# mtp_zesilovac.net
KiCad netlist of a schematic drawn in EAGLE
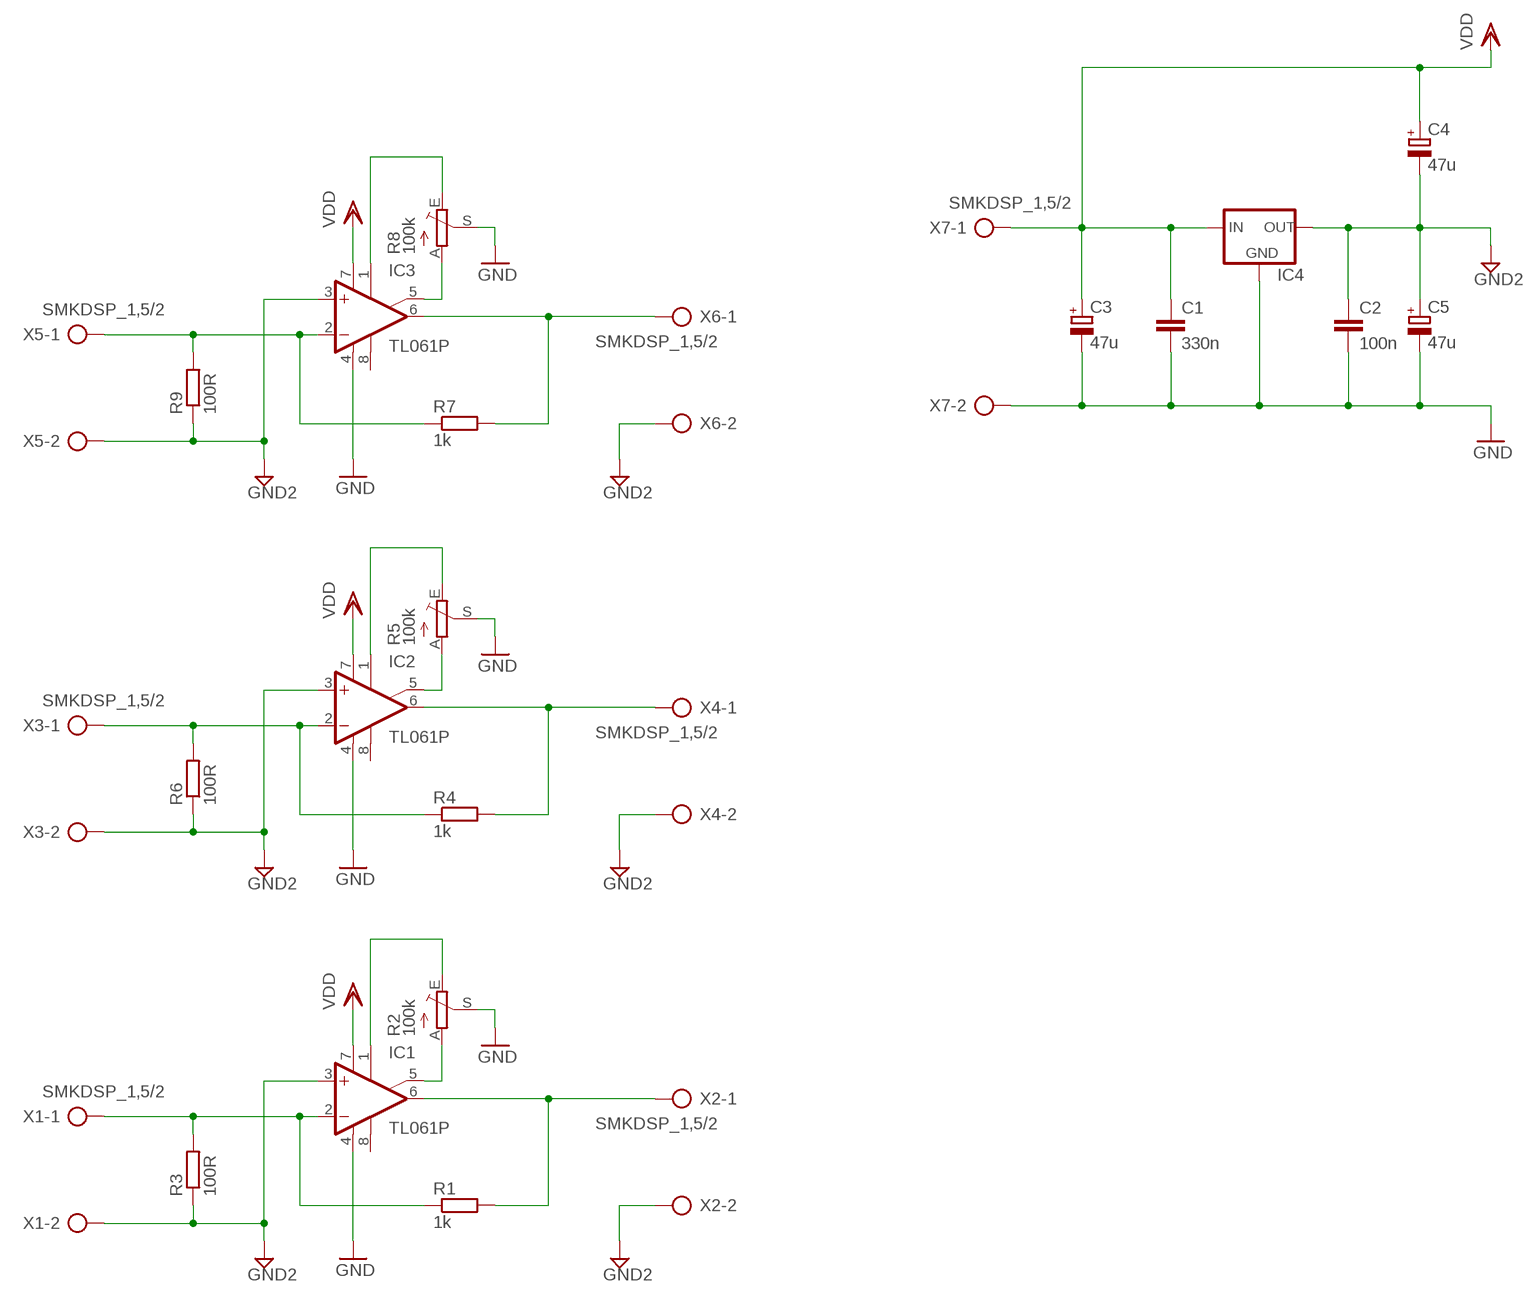
[diagram p0: schematic, sheet 1]

(export (version "E")
  (design (tool "Eeschema 10.0.6"))
  (components
    (comp (ref "C1")
      (value "330n")
      (footprint "eagle-import:C050-045X075")
      (libsource (lib "eagle-import") (part "C-EU050-045X075"))
    )
    (comp (ref "C2")
      (value "100n")
      (footprint "eagle-import:C050-045X075")
      (libsource (lib "eagle-import") (part "C-EU050-045X075"))
    )
    (comp (ref "C3")
      (value "47u")
      (footprint "eagle-import:E2,5-7")
      (libsource (lib "eagle-import") (part "CPOL-EUE2.5-7"))
    )
    (comp (ref "C4")
      (value "47u")
      (footprint "eagle-import:E2,5-7")
      (libsource (lib "eagle-import") (part "CPOL-EUE2.5-7"))
    )
    (comp (ref "C5")
      (value "47u")
      (footprint "eagle-import:E2,5-7")
      (libsource (lib "eagle-import") (part "CPOL-EUE2.5-7"))
    )
    (comp (ref "IC1")
      (value "TL061P")
      (footprint "eagle-import:DIL08")
      (libsource (lib "eagle-import") (part "TL061P"))
    )
    (comp (ref "IC2")
      (value "TL061P")
      (footprint "eagle-import:DIL08")
      (libsource (lib "eagle-import") (part "TL061P"))
    )
    (comp (ref "IC3")
      (value "TL061P")
      (footprint "eagle-import:DIL08")
      (libsource (lib "eagle-import") (part "TL061P"))
    )
    (comp (ref "IC4")
      (value "78LXX")
      (footprint "eagle-import:78LXX")
      (libsource (lib "eagle-import") (part "78LXX"))
    )
    (comp (ref "R1")
      (value "1k")
      (footprint "eagle-import:0207_12")
      (libsource (lib "eagle-import") (part "R-EU_0207/12"))
    )
    (comp (ref "R2")
      (value "100k")
      (footprint "eagle-import:LI10")
      (libsource (lib "eagle-import") (part "TRIM_EU-LI10"))
    )
    (comp (ref "R3")
      (value "100R")
      (footprint "eagle-import:0207_12")
      (libsource (lib "eagle-import") (part "R-EU_0207/12"))
    )
    (comp (ref "R4")
      (value "1k")
      (footprint "eagle-import:0207_12")
      (libsource (lib "eagle-import") (part "R-EU_0207/12"))
    )
    (comp (ref "R5")
      (value "100k")
      (footprint "eagle-import:LI10")
      (libsource (lib "eagle-import") (part "TRIM_EU-LI10"))
    )
    (comp (ref "R6")
      (value "100R")
      (footprint "eagle-import:0207_12")
      (libsource (lib "eagle-import") (part "R-EU_0207/12"))
    )
    (comp (ref "R7")
      (value "1k")
      (footprint "eagle-import:0207_12")
      (libsource (lib "eagle-import") (part "R-EU_0207/12"))
    )
    (comp (ref "R8")
      (value "100k")
      (footprint "eagle-import:LI10")
      (libsource (lib "eagle-import") (part "TRIM_EU-LI10"))
    )
    (comp (ref "R9")
      (value "100R")
      (footprint "eagle-import:0207_12")
      (libsource (lib "eagle-import") (part "R-EU_0207/12"))
    )
    (comp (ref "X1")
      (value "SMKDSP_1,5/2")
      (footprint "eagle-import:SMKDSP_1,5_2")
      (fields (field (name "MF") "FARNELL") (field (name "MPN") "1733570"))
      (libsource (lib "eagle-import") (part "SMKDSP_1,5/2"))
    )
    (comp (ref "X2")
      (value "SMKDSP_1,5/2")
      (footprint "eagle-import:SMKDSP_1,5_2")
      (fields (field (name "MF") "FARNELL") (field (name "MPN") "1733570"))
      (libsource (lib "eagle-import") (part "SMKDSP_1,5/2"))
    )
    (comp (ref "X3")
      (value "SMKDSP_1,5/2")
      (footprint "eagle-import:SMKDSP_1,5_2")
      (fields (field (name "MF") "FARNELL") (field (name "MPN") "1733570"))
      (libsource (lib "eagle-import") (part "SMKDSP_1,5/2"))
    )
    (comp (ref "X4")
      (value "SMKDSP_1,5/2")
      (footprint "eagle-import:SMKDSP_1,5_2")
      (fields (field (name "MF") "FARNELL") (field (name "MPN") "1733570"))
      (libsource (lib "eagle-import") (part "SMKDSP_1,5/2"))
    )
    (comp (ref "X5")
      (value "SMKDSP_1,5/2")
      (footprint "eagle-import:SMKDSP_1,5_2")
      (fields (field (name "MF") "FARNELL") (field (name "MPN") "1733570"))
      (libsource (lib "eagle-import") (part "SMKDSP_1,5/2"))
    )
    (comp (ref "X6")
      (value "SMKDSP_1,5/2")
      (footprint "eagle-import:SMKDSP_1,5_2")
      (fields (field (name "MF") "FARNELL") (field (name "MPN") "1733570"))
      (libsource (lib "eagle-import") (part "SMKDSP_1,5/2"))
    )
    (comp (ref "X7")
      (value "SMKDSP_1,5/2")
      (footprint "eagle-import:SMKDSP_1,5_2")
      (fields (field (name "MF") "FARNELL") (field (name "MPN") "1733570"))
      (libsource (lib "eagle-import") (part "SMKDSP_1,5/2"))
    )
  )
  (nets
    (net (code "1") (name "GND") (class "Default")
      (node (ref "C1") (pin "2") (pinfunction "2_2") (pintype "passive"))
      (node (ref "C2") (pin "2") (pinfunction "2_2") (pintype "passive"))
      (node (ref "C3") (pin "-") (pinfunction "-_-") (pintype "passive"))
      (node (ref "C5") (pin "-") (pinfunction "-_-") (pintype "passive"))
      (node (ref "IC1") (pin "4") (pinfunction "V-_4") (pintype "power_in"))
      (node (ref "IC2") (pin "4") (pinfunction "V-_4") (pintype "power_in"))
      (node (ref "IC3") (pin "4") (pinfunction "V-_4") (pintype "power_in"))
      (node (ref "IC4") (pin "GND") (pinfunction "GND_GND") (pintype "input"))
      (node (ref "R2") (pin "S") (pinfunction "S_S") (pintype "passive"))
      (node (ref "R5") (pin "S") (pinfunction "S_S") (pintype "passive"))
      (node (ref "R8") (pin "S") (pinfunction "S_S") (pintype "passive"))
      (node (ref "X7") (pin "2") (pinfunction "KL_2") (pintype "passive"))
    )
    (net (code "2") (name "GND2") (class "Default")
      (node (ref "C2") (pin "1") (pinfunction "1_1") (pintype "passive"))
      (node (ref "C4") (pin "-") (pinfunction "-_-") (pintype "passive"))
      (node (ref "C5") (pin "+") (pinfunction "+_+") (pintype "passive"))
      (node (ref "IC1") (pin "3") (pinfunction "+IN_3") (pintype "input"))
      (node (ref "IC2") (pin "3") (pinfunction "+IN_3") (pintype "input"))
      (node (ref "IC3") (pin "3") (pinfunction "+IN_3") (pintype "input"))
      (node (ref "IC4") (pin "OUT") (pinfunction "OUT_OUT") (pintype "passive"))
      (node (ref "R3") (pin "1") (pinfunction "1_1") (pintype "passive"))
      (node (ref "R6") (pin "1") (pinfunction "1_1") (pintype "passive"))
      (node (ref "R9") (pin "1") (pinfunction "1_1") (pintype "passive"))
      (node (ref "X1") (pin "2") (pinfunction "KL_2") (pintype "passive"))
      (node (ref "X2") (pin "2") (pinfunction "KL_2") (pintype "passive"))
      (node (ref "X3") (pin "2") (pinfunction "KL_2") (pintype "passive"))
      (node (ref "X4") (pin "2") (pinfunction "KL_2") (pintype "passive"))
      (node (ref "X5") (pin "2") (pinfunction "KL_2") (pintype "passive"))
      (node (ref "X6") (pin "2") (pinfunction "KL_2") (pintype "passive"))
    )
    (net (code "3") (name "Net-(IC1--IN)") (class "Default")
      (node (ref "IC1") (pin "2") (pinfunction "-IN_2") (pintype "input"))
      (node (ref "R1") (pin "1") (pinfunction "1_1") (pintype "passive"))
      (node (ref "R3") (pin "2") (pinfunction "2_2") (pintype "passive"))
      (node (ref "X1") (pin "1") (pinfunction "KL_1") (pintype "passive"))
    )
    (net (code "4") (name "Net-(IC1-ON1)") (class "Default")
      (node (ref "IC1") (pin "1") (pinfunction "ON1_1") (pintype "passive"))
      (node (ref "R2") (pin "E") (pinfunction "E_E") (pintype "passive"))
    )
    (net (code "5") (name "Net-(IC1-ON2)") (class "Default")
      (node (ref "IC1") (pin "5") (pinfunction "ON2_5") (pintype "passive"))
      (node (ref "R2") (pin "A") (pinfunction "A_A") (pintype "passive"))
    )
    (net (code "6") (name "Net-(IC1-OUT)") (class "Default")
      (node (ref "IC1") (pin "6") (pinfunction "OUT_6") (pintype "output"))
      (node (ref "R1") (pin "2") (pinfunction "2_2") (pintype "passive"))
      (node (ref "X2") (pin "1") (pinfunction "KL_1") (pintype "passive"))
    )
    (net (code "7") (name "Net-(IC2--IN)") (class "Default")
      (node (ref "IC2") (pin "2") (pinfunction "-IN_2") (pintype "input"))
      (node (ref "R4") (pin "1") (pinfunction "1_1") (pintype "passive"))
      (node (ref "R6") (pin "2") (pinfunction "2_2") (pintype "passive"))
      (node (ref "X3") (pin "1") (pinfunction "KL_1") (pintype "passive"))
    )
    (net (code "8") (name "Net-(IC2-ON1)") (class "Default")
      (node (ref "IC2") (pin "1") (pinfunction "ON1_1") (pintype "passive"))
      (node (ref "R5") (pin "E") (pinfunction "E_E") (pintype "passive"))
    )
    (net (code "9") (name "Net-(IC2-ON2)") (class "Default")
      (node (ref "IC2") (pin "5") (pinfunction "ON2_5") (pintype "passive"))
      (node (ref "R5") (pin "A") (pinfunction "A_A") (pintype "passive"))
    )
    (net (code "10") (name "Net-(IC2-OUT)") (class "Default")
      (node (ref "IC2") (pin "6") (pinfunction "OUT_6") (pintype "output"))
      (node (ref "R4") (pin "2") (pinfunction "2_2") (pintype "passive"))
      (node (ref "X4") (pin "1") (pinfunction "KL_1") (pintype "passive"))
    )
    (net (code "11") (name "Net-(IC3--IN)") (class "Default")
      (node (ref "IC3") (pin "2") (pinfunction "-IN_2") (pintype "input"))
      (node (ref "R7") (pin "1") (pinfunction "1_1") (pintype "passive"))
      (node (ref "R9") (pin "2") (pinfunction "2_2") (pintype "passive"))
      (node (ref "X5") (pin "1") (pinfunction "KL_1") (pintype "passive"))
    )
    (net (code "12") (name "Net-(IC3-ON1)") (class "Default")
      (node (ref "IC3") (pin "1") (pinfunction "ON1_1") (pintype "passive"))
      (node (ref "R8") (pin "E") (pinfunction "E_E") (pintype "passive"))
    )
    (net (code "13") (name "Net-(IC3-ON2)") (class "Default")
      (node (ref "IC3") (pin "5") (pinfunction "ON2_5") (pintype "passive"))
      (node (ref "R8") (pin "A") (pinfunction "A_A") (pintype "passive"))
    )
    (net (code "14") (name "Net-(IC3-OUT)") (class "Default")
      (node (ref "IC3") (pin "6") (pinfunction "OUT_6") (pintype "output"))
      (node (ref "R7") (pin "2") (pinfunction "2_2") (pintype "passive"))
      (node (ref "X6") (pin "1") (pinfunction "KL_1") (pintype "passive"))
    )
    (net (code "15") (name "VDD") (class "Default")
      (node (ref "C1") (pin "1") (pinfunction "1_1") (pintype "passive"))
      (node (ref "C3") (pin "+") (pinfunction "+_+") (pintype "passive"))
      (node (ref "C4") (pin "+") (pinfunction "+_+") (pintype "passive"))
      (node (ref "IC1") (pin "7") (pinfunction "V+_7") (pintype "power_in"))
      (node (ref "IC2") (pin "7") (pinfunction "V+_7") (pintype "power_in"))
      (node (ref "IC3") (pin "7") (pinfunction "V+_7") (pintype "power_in"))
      (node (ref "IC4") (pin "IN") (pinfunction "IN_IN") (pintype "input"))
      (node (ref "X7") (pin "1") (pinfunction "KL_1") (pintype "passive"))
    )
    (net (code "16") (name "unconnected-(IC1-OPT-Pad8)") (class "Default")
      (node (ref "IC1") (pin "8") (pinfunction "OPT_8") (pintype "passive"))
    )
    (net (code "17") (name "unconnected-(IC2-OPT-Pad8)") (class "Default")
      (node (ref "IC2") (pin "8") (pinfunction "OPT_8") (pintype "passive"))
    )
    (net (code "18") (name "unconnected-(IC3-OPT-Pad8)") (class "Default")
      (node (ref "IC3") (pin "8") (pinfunction "OPT_8") (pintype "passive"))
    )
  )
)
